# Sheet_1.net
KiCad netlist of a schematic drawn in EasyEDA
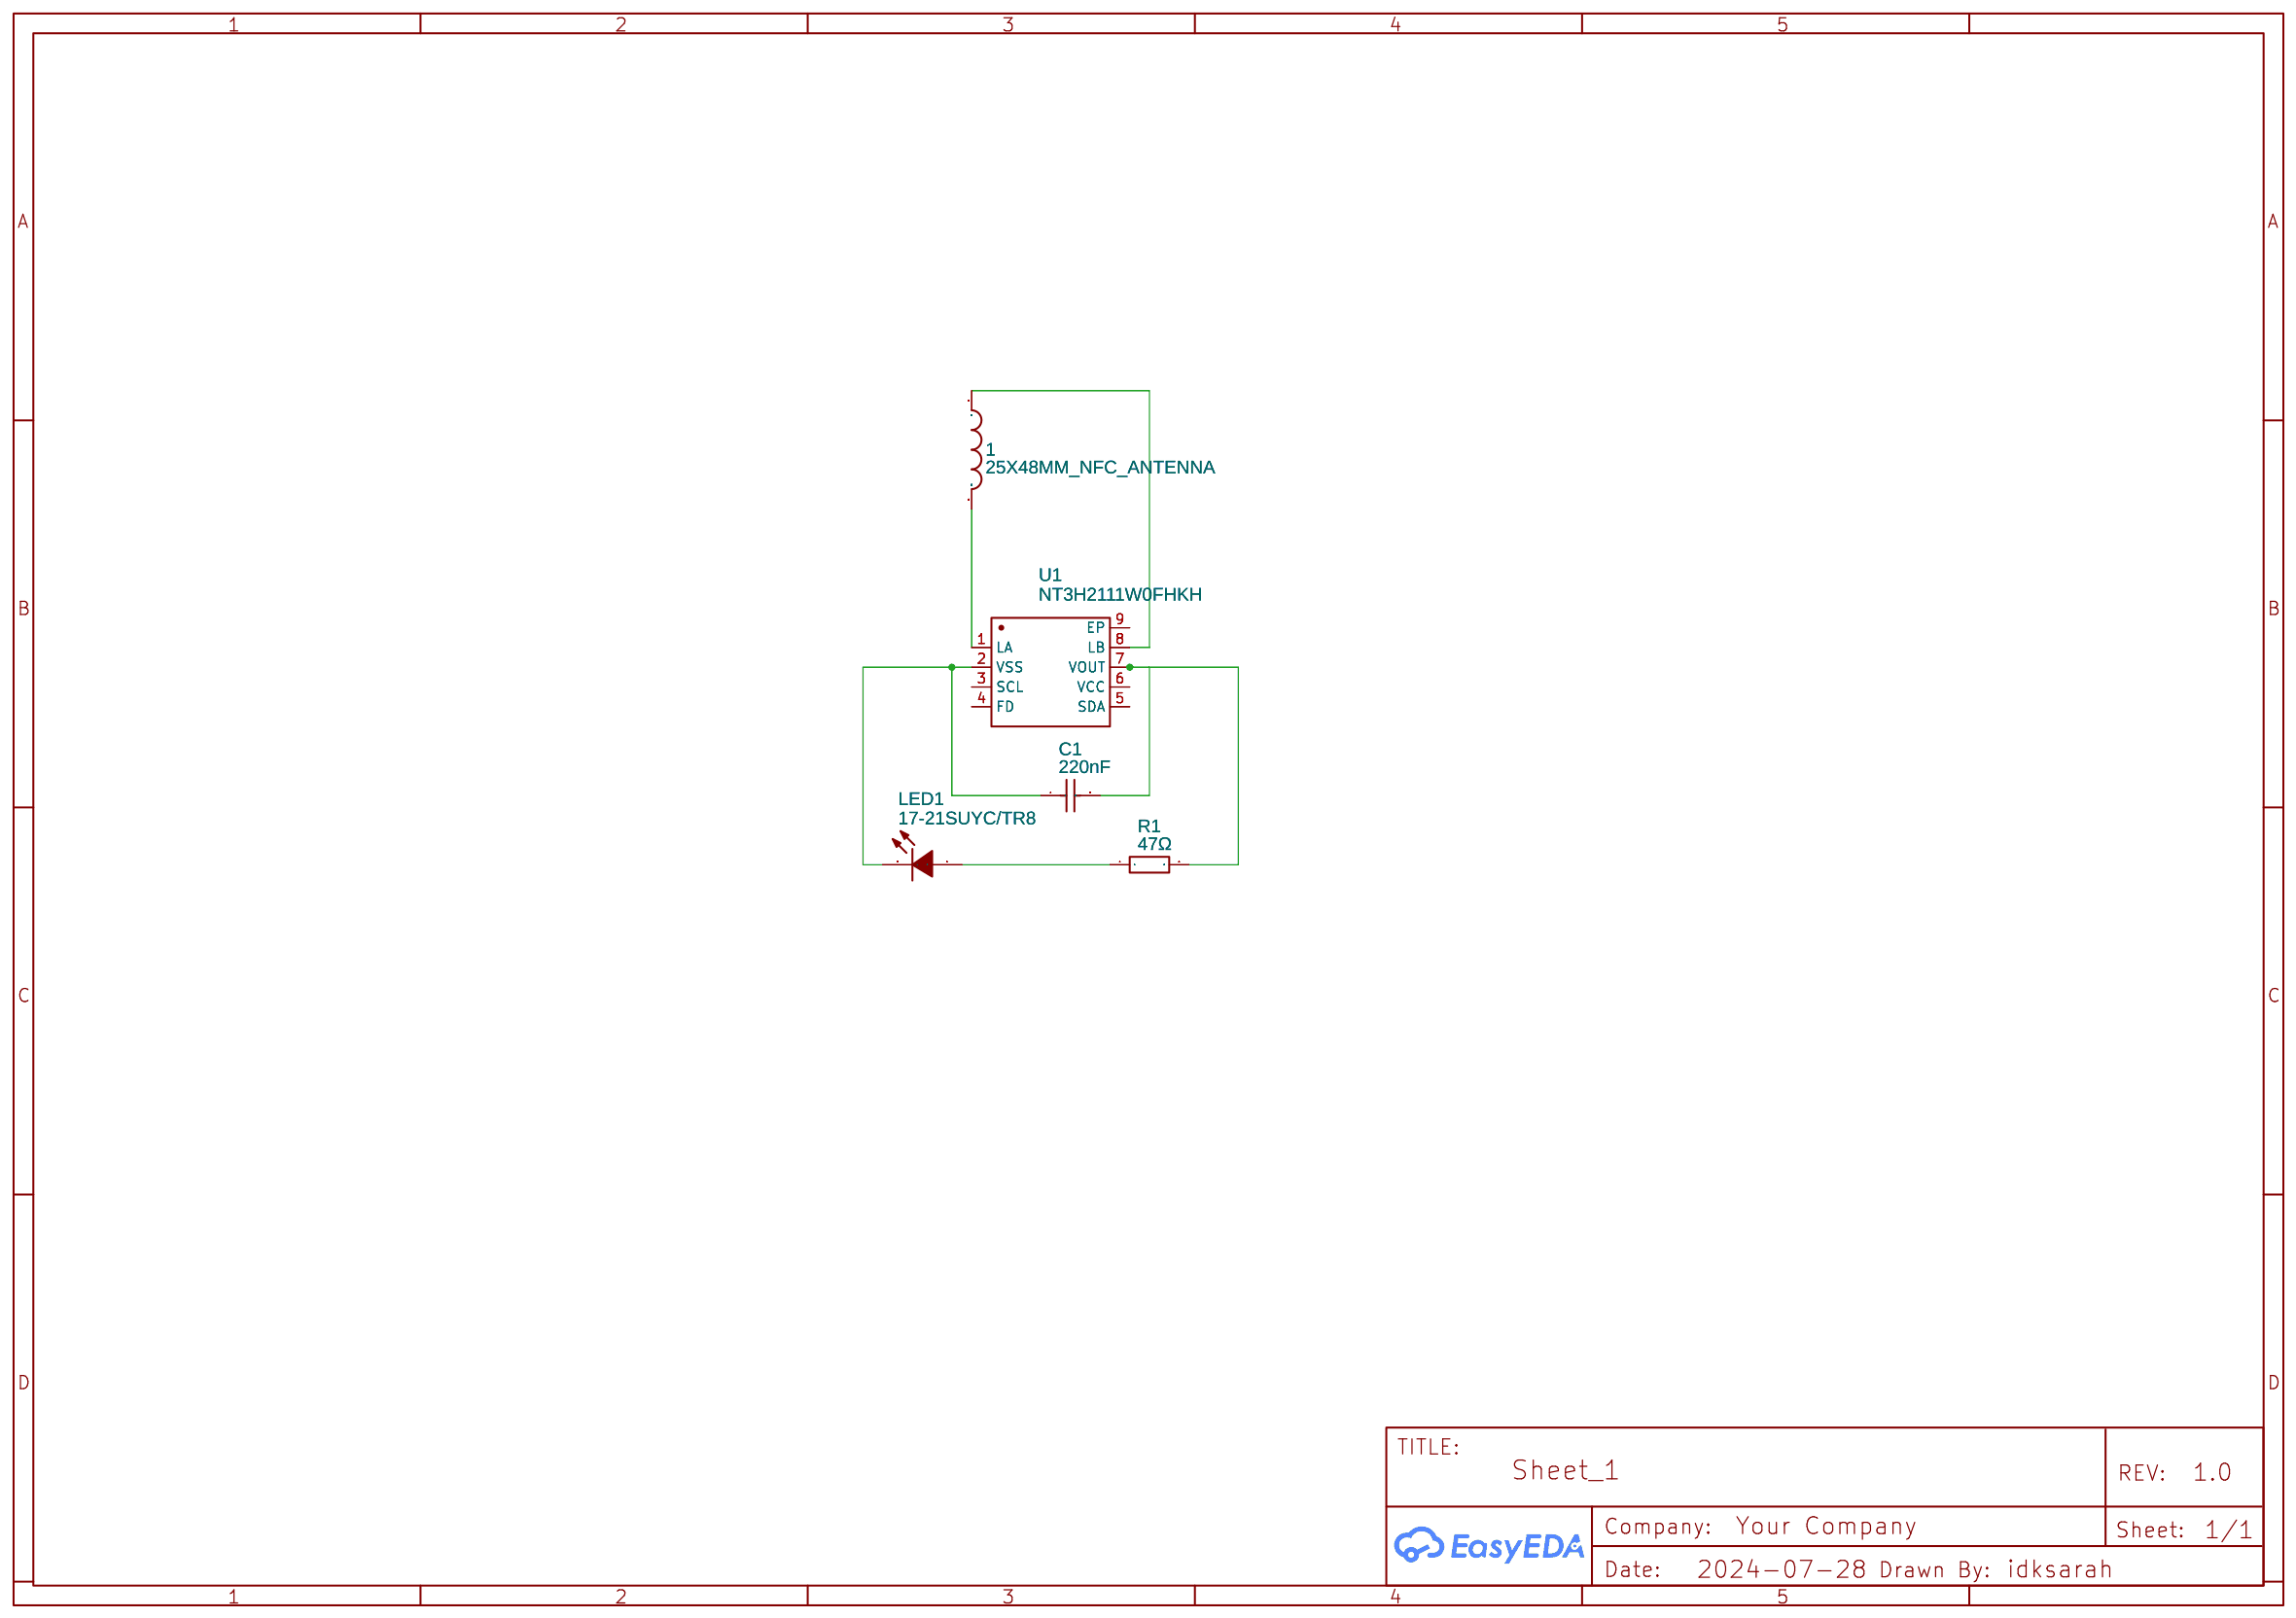
[diagram p0: schematic sheet]

(export (version "E")
  (design (tool "Eeschema 10.0.6"))
  (components
    (comp (ref "1") (value "25X48MM_NFC_ANTENNA") (libsource (lib "") (part "25X48MM_NFC_ANTENNA")))
    (comp (ref "C1")
      (value "220nF")
      (fields
        (field (name "Manufacturer Part") "CL10B224KA8NNNC")
        (field (name "Manufacturer") "SAMSUNG(三星)")
      )
      (libsource (lib "") (part "CL10B224KA8NNNC"))
    )
    (comp (ref "LED1")
      (value "17-21SUYC/TR8")
      (fields (field (name "Manufacturer Part") "KT-0805黄灯") (field (name "Manufacturer") "KENTO"))
      (libsource (lib "") (part "17-21SUYC/TR8"))
    )
    (comp (ref "R1")
      (value "47Ω")
      (fields
        (field (name "Manufacturer Part") "0603WAF470JT5E")
        (field (name "Manufacturer") "UNI-ROYAL(厚声)")
      )
      (libsource (lib "") (part "0603WAF470JT5E"))
    )
    (comp (ref "U1")
      (value "NT3H2111W0FHKH")
      (fields (field (name "Manufacturer") "NXP(恩智浦)"))
      (libsource (lib "") (part "NT3H2111W0FHKH"))
    )
  )
  (nets
    (net (code "1") (name "Net-(LED1-+)") (class "Default")
      (node (ref "LED1") (pin "1") (pinfunction "+_1") (pintype "unspecified"))
      (node (ref "R1") (pin "1") (pinfunction "1_1") (pintype "input"))
    )
    (net (code "2") (name "Net-(LED1--)") (class "Default")
      (node (ref "C1") (pin "1") (pinfunction "1_1") (pintype "input"))
      (node (ref "LED1") (pin "2") (pinfunction "-_2") (pintype "unspecified"))
      (node (ref "U1") (pin "2") (pinfunction "VSS_2") (pintype "unspecified"))
    )
    (net (code "3") (name "Net-(U1-LA)") (class "Default")
      (node (ref "1") (pin "P$2") (pinfunction "P$2_P$2") (pintype "bidirectional"))
      (node (ref "U1") (pin "1") (pinfunction "LA_1") (pintype "unspecified"))
    )
    (net (code "4") (name "Net-(U1-LB)") (class "Default")
      (node (ref "1") (pin "P$1") (pinfunction "P$1_P$1") (pintype "bidirectional"))
      (node (ref "U1") (pin "8") (pinfunction "LB_8") (pintype "unspecified"))
    )
    (net (code "5") (name "Net-(U1-VOUT)") (class "Default")
      (node (ref "C1") (pin "2") (pinfunction "2_2") (pintype "input"))
      (node (ref "R1") (pin "2") (pinfunction "2_2") (pintype "input"))
      (node (ref "U1") (pin "7") (pinfunction "VOUT_7") (pintype "unspecified"))
    )
    (net (code "6") (name "unconnected-(U1-EP-Pad9)") (class "Default")
      (node (ref "U1") (pin "9") (pinfunction "EP_9") (pintype "unspecified"))
    )
    (net (code "7") (name "unconnected-(U1-FD-Pad4)") (class "Default")
      (node (ref "U1") (pin "4") (pinfunction "FD_4") (pintype "unspecified"))
    )
    (net (code "8") (name "unconnected-(U1-SCL-Pad3)") (class "Default")
      (node (ref "U1") (pin "3") (pinfunction "SCL_3") (pintype "unspecified"))
    )
    (net (code "9") (name "unconnected-(U1-SDA-Pad5)") (class "Default")
      (node (ref "U1") (pin "5") (pinfunction "SDA_5") (pintype "unspecified"))
    )
    (net (code "10") (name "unconnected-(U1-VCC-Pad6)") (class "Default")
      (node (ref "U1") (pin "6") (pinfunction "VCC_6") (pintype "unspecified"))
    )
  )
)
